# Atmega328p_sismin_attempt_4.net
KiCad netlist of a schematic drawn in EAGLE
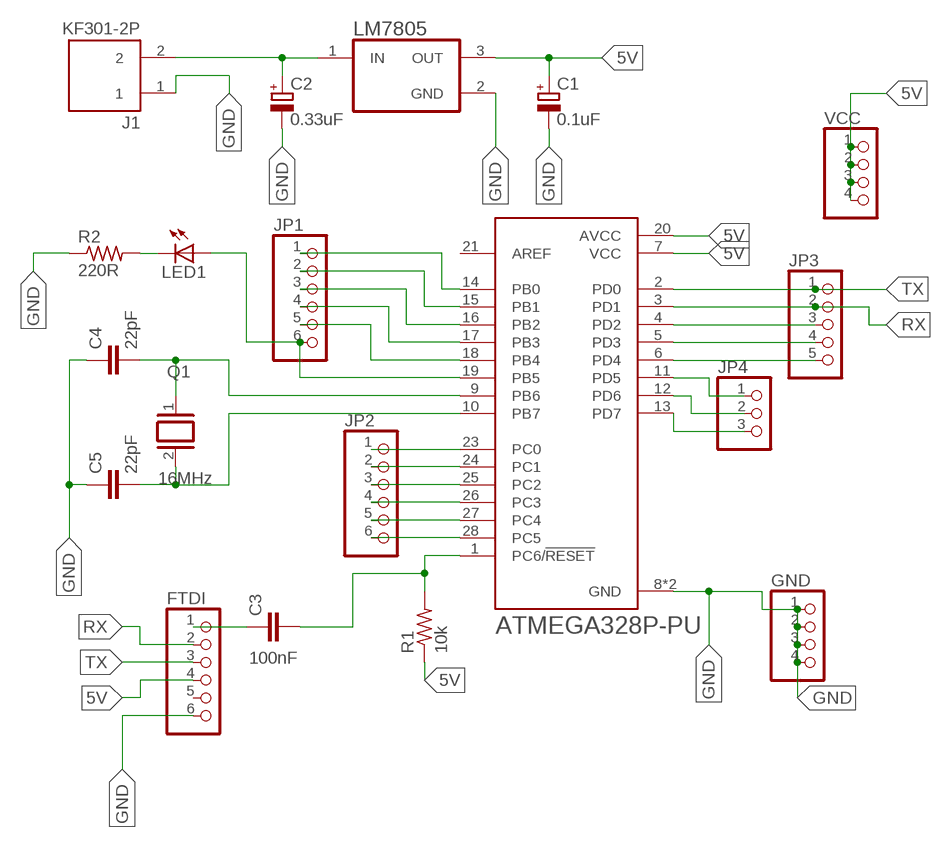
[diagram p0: schematic, sheet 1]

(export (version "E")
  (design (tool "Eeschema 10.0.6"))
  (components
    (comp (ref "C1")
      (value "0.1uF")
      (footprint "eagle-import:E2,5-6")
      (libsource (lib "eagle-import") (part "CPOL-EUE2.5-6"))
    )
    (comp (ref "C2")
      (value "0.33uF")
      (footprint "eagle-import:E2,5-6")
      (libsource (lib "eagle-import") (part "CPOL-EUE2.5-6"))
    )
    (comp (ref "C3")
      (value "100nF")
      (footprint "eagle-import:C050-025X075")
      (libsource (lib "eagle-import") (part "C-EU050-025X075"))
    )
    (comp (ref "C4")
      (value "22pF")
      (footprint "eagle-import:C025-025X050")
      (libsource (lib "eagle-import") (part "C-EU025-025X050"))
    )
    (comp (ref "C5")
      (value "22pF")
      (footprint "eagle-import:C025-025X050")
      (libsource (lib "eagle-import") (part "C-EU025-025X050"))
    )
    (comp (ref "FTDI")
      (value "PINHD-1X6")
      (footprint "eagle-import:1X06")
      (libsource (lib "eagle-import") (part "PINHD-1X6"))
    )
    (comp (ref "GND")
      (value "PINHD-1X4")
      (footprint "eagle-import:1X04")
      (libsource (lib "eagle-import") (part "PINHD-1X4"))
    )
    (comp (ref "J1")
      (value "KF301-2P")
      (footprint "eagle-import:HANDSON_KF301-2P")
      (fields (field (name "MF") "Handson Technology"))
      (libsource (lib "eagle-import") (part "KF301-2P"))
    )
    (comp (ref "JP1")
      (value "PINHD-1X6")
      (footprint "eagle-import:1X06")
      (libsource (lib "eagle-import") (part "PINHD-1X6"))
    )
    (comp (ref "JP2")
      (value "PINHD-1X6")
      (footprint "eagle-import:1X06")
      (libsource (lib "eagle-import") (part "PINHD-1X6"))
    )
    (comp (ref "JP3")
      (value "PINHD-1X5")
      (footprint "eagle-import:1X05")
      (libsource (lib "eagle-import") (part "PINHD-1X5"))
    )
    (comp (ref "JP4")
      (value "PINHD-1X3")
      (footprint "eagle-import:1X03")
      (libsource (lib "eagle-import") (part "PINHD-1X3"))
    )
    (comp (ref "LED1")
      (value "LED5MM")
      (footprint "eagle-import:LED5MM")
      (libsource (lib "eagle-import") (part "LED5MM"))
    )
    (comp (ref "LM7805")
      (value "LM7805CT/NOPB")
      (footprint "eagle-import:TO254P1054X470X2600-3")
      (fields (field (name "MF") "ON Semiconductor") (field (name "MP") "LM7805CT"))
      (libsource (lib "eagle-import") (part "LM7805CT/NOPB"))
    )
    (comp (ref "Q1")
      (value "16MHz")
      (footprint "eagle-import:QS")
      (libsource (lib "eagle-import") (part "XTAL/S"))
    )
    (comp (ref "R1")
      (value "10k")
      (footprint "eagle-import:0207_7")
      (libsource (lib "eagle-import") (part "R-US_0207/7"))
    )
    (comp (ref "R2")
      (value "220R")
      (footprint "eagle-import:0204_7")
      (libsource (lib "eagle-import") (part "R-US_0204/7"))
    )
    (comp (ref "U1")
      (value "ATMEGA328P-PU")
      (footprint "eagle-import:DIP794W46P254L2967H457Q28B")
      (fields (field (name "MF") "Microchip"))
      (libsource (lib "eagle-import") (part "ATMEGA328P-PU"))
    )
    (comp (ref "VCC")
      (value "PINHD-1X4")
      (footprint "eagle-import:1X04")
      (libsource (lib "eagle-import") (part "PINHD-1X4"))
    )
  )
  (nets
    (net (code "1") (name "5V") (class "Default")
      (node (ref "C1") (pin "+") (pinfunction "+_+") (pintype "passive"))
      (node (ref "FTDI") (pin "4") (pinfunction "4_4") (pintype "passive"))
      (node (ref "LM7805") (pin "3") (pinfunction "OUT_3") (pintype "output"))
      (node (ref "R1") (pin "1") (pinfunction "1_1") (pintype "passive"))
      (node (ref "U1") (pin "20") (pinfunction "AVCC_20") (pintype "power_in"))
      (node (ref "U1") (pin "7") (pinfunction "VCC_7") (pintype "power_in"))
      (node (ref "VCC") (pin "1") (pinfunction "1_1") (pintype "passive"))
      (node (ref "VCC") (pin "2") (pinfunction "2_2") (pintype "passive"))
      (node (ref "VCC") (pin "3") (pinfunction "3_3") (pintype "passive"))
      (node (ref "VCC") (pin "4") (pinfunction "4_4") (pintype "passive"))
    )
    (net (code "2") (name "GND") (class "Default")
      (node (ref "C1") (pin "-") (pinfunction "-_-") (pintype "passive"))
      (node (ref "C2") (pin "-") (pinfunction "-_-") (pintype "passive"))
      (node (ref "C4") (pin "1") (pinfunction "1_1") (pintype "passive"))
      (node (ref "C5") (pin "1") (pinfunction "1_1") (pintype "passive"))
      (node (ref "FTDI") (pin "6") (pinfunction "6_6") (pintype "passive"))
      (node (ref "GND") (pin "1") (pinfunction "1_1") (pintype "passive"))
      (node (ref "GND") (pin "2") (pinfunction "2_2") (pintype "passive"))
      (node (ref "GND") (pin "3") (pinfunction "3_3") (pintype "passive"))
      (node (ref "GND") (pin "4") (pinfunction "4_4") (pintype "passive"))
      (node (ref "J1") (pin "1") (pinfunction "1_1") (pintype "passive"))
      (node (ref "LM7805") (pin "2") (pinfunction "GND_2") (pintype "power_in"))
      (node (ref "R2") (pin "1") (pinfunction "1_1") (pintype "passive"))
      (node (ref "U1") (pin "22") (pinfunction "GND_22") (pintype "power_in"))
      (node (ref "U1") (pin "8") (pinfunction "GND_8") (pintype "power_in"))
    )
    (net (code "3") (name "Net-(C3-Pad1)") (class "Default")
      (node (ref "C3") (pin "1") (pinfunction "1_1") (pintype "passive"))
      (node (ref "FTDI") (pin "1") (pinfunction "1_1") (pintype "passive"))
    )
    (net (code "4") (name "Net-(LED1-C)") (class "Default")
      (node (ref "LED1") (pin "K") (pinfunction "C_K") (pintype "passive"))
      (node (ref "R2") (pin "2") (pinfunction "2_2") (pintype "passive"))
    )
    (net (code "5") (name "Net-(LM7805-IN)") (class "Default")
      (node (ref "C2") (pin "+") (pinfunction "+_+") (pintype "passive"))
      (node (ref "J1") (pin "2") (pinfunction "2_2") (pintype "passive"))
      (node (ref "LM7805") (pin "1") (pinfunction "IN_1") (pintype "input"))
    )
    (net (code "6") (name "Net-(U1-PB0)") (class "Default")
      (node (ref "JP1") (pin "1") (pinfunction "1_1") (pintype "passive"))
      (node (ref "U1") (pin "14") (pinfunction "PB0_14") (pintype "bidirectional"))
    )
    (net (code "7") (name "Net-(U1-PB1)") (class "Default")
      (node (ref "JP1") (pin "2") (pinfunction "2_2") (pintype "passive"))
      (node (ref "U1") (pin "15") (pinfunction "PB1_15") (pintype "bidirectional"))
    )
    (net (code "8") (name "Net-(U1-PB2)") (class "Default")
      (node (ref "JP1") (pin "3") (pinfunction "3_3") (pintype "passive"))
      (node (ref "U1") (pin "16") (pinfunction "PB2_16") (pintype "bidirectional"))
    )
    (net (code "9") (name "Net-(U1-PB3)") (class "Default")
      (node (ref "JP1") (pin "4") (pinfunction "4_4") (pintype "passive"))
      (node (ref "U1") (pin "17") (pinfunction "PB3_17") (pintype "bidirectional"))
    )
    (net (code "10") (name "Net-(U1-PB4)") (class "Default")
      (node (ref "JP1") (pin "5") (pinfunction "5_5") (pintype "passive"))
      (node (ref "U1") (pin "18") (pinfunction "PB4_18") (pintype "bidirectional"))
    )
    (net (code "11") (name "Net-(U1-PB5)") (class "Default")
      (node (ref "JP1") (pin "6") (pinfunction "6_6") (pintype "passive"))
      (node (ref "LED1") (pin "A") (pinfunction "A_A") (pintype "passive"))
      (node (ref "U1") (pin "19") (pinfunction "PB5_19") (pintype "bidirectional"))
    )
    (net (code "12") (name "Net-(U1-PB6)") (class "Default")
      (node (ref "C4") (pin "2") (pinfunction "2_2") (pintype "passive"))
      (node (ref "Q1") (pin "1") (pinfunction "1_1") (pintype "passive"))
      (node (ref "U1") (pin "9") (pinfunction "PB6_9") (pintype "bidirectional"))
    )
    (net (code "13") (name "Net-(U1-PB7)") (class "Default")
      (node (ref "C5") (pin "2") (pinfunction "2_2") (pintype "passive"))
      (node (ref "Q1") (pin "2") (pinfunction "2_2") (pintype "passive"))
      (node (ref "U1") (pin "10") (pinfunction "PB7_10") (pintype "bidirectional"))
    )
    (net (code "14") (name "Net-(U1-PC0)") (class "Default")
      (node (ref "JP2") (pin "1") (pinfunction "1_1") (pintype "passive"))
      (node (ref "U1") (pin "23") (pinfunction "PC0_23") (pintype "bidirectional"))
    )
    (net (code "15") (name "Net-(U1-PC1)") (class "Default")
      (node (ref "JP2") (pin "2") (pinfunction "2_2") (pintype "passive"))
      (node (ref "U1") (pin "24") (pinfunction "PC1_24") (pintype "bidirectional"))
    )
    (net (code "16") (name "Net-(U1-PC2)") (class "Default")
      (node (ref "JP2") (pin "3") (pinfunction "3_3") (pintype "passive"))
      (node (ref "U1") (pin "25") (pinfunction "PC2_25") (pintype "bidirectional"))
    )
    (net (code "17") (name "Net-(U1-PC3)") (class "Default")
      (node (ref "JP2") (pin "4") (pinfunction "4_4") (pintype "passive"))
      (node (ref "U1") (pin "26") (pinfunction "PC3_26") (pintype "bidirectional"))
    )
    (net (code "18") (name "Net-(U1-PC4)") (class "Default")
      (node (ref "JP2") (pin "5") (pinfunction "5_5") (pintype "passive"))
      (node (ref "U1") (pin "27") (pinfunction "PC4_27") (pintype "bidirectional"))
    )
    (net (code "19") (name "Net-(U1-PC5)") (class "Default")
      (node (ref "JP2") (pin "6") (pinfunction "6_6") (pintype "passive"))
      (node (ref "U1") (pin "28") (pinfunction "PC5_28") (pintype "bidirectional"))
    )
    (net (code "20") (name "Net-(U1-PC6{slash}~{RESET})") (class "Default")
      (node (ref "C3") (pin "2") (pinfunction "2_2") (pintype "passive"))
      (node (ref "R1") (pin "2") (pinfunction "2_2") (pintype "passive"))
      (node (ref "U1") (pin "1") (pinfunction "PC6/~{RESET}_1") (pintype "bidirectional"))
    )
    (net (code "21") (name "Net-(U1-PD2)") (class "Default")
      (node (ref "JP3") (pin "3") (pinfunction "3_3") (pintype "passive"))
      (node (ref "U1") (pin "4") (pinfunction "PD2_4") (pintype "bidirectional"))
    )
    (net (code "22") (name "Net-(U1-PD3)") (class "Default")
      (node (ref "JP3") (pin "4") (pinfunction "4_4") (pintype "passive"))
      (node (ref "U1") (pin "5") (pinfunction "PD3_5") (pintype "bidirectional"))
    )
    (net (code "23") (name "Net-(U1-PD4)") (class "Default")
      (node (ref "JP3") (pin "5") (pinfunction "5_5") (pintype "passive"))
      (node (ref "U1") (pin "6") (pinfunction "PD4_6") (pintype "bidirectional"))
    )
    (net (code "24") (name "Net-(U1-PD5)") (class "Default")
      (node (ref "JP4") (pin "1") (pinfunction "1_1") (pintype "passive"))
      (node (ref "U1") (pin "11") (pinfunction "PD5_11") (pintype "bidirectional"))
    )
    (net (code "25") (name "Net-(U1-PD6)") (class "Default")
      (node (ref "JP4") (pin "2") (pinfunction "2_2") (pintype "passive"))
      (node (ref "U1") (pin "12") (pinfunction "PD6_12") (pintype "bidirectional"))
    )
    (net (code "26") (name "Net-(U1-PD7)") (class "Default")
      (node (ref "JP4") (pin "3") (pinfunction "3_3") (pintype "passive"))
      (node (ref "U1") (pin "13") (pinfunction "PD7_13") (pintype "bidirectional"))
    )
    (net (code "27") (name "RX") (class "Default")
      (node (ref "FTDI") (pin "2") (pinfunction "2_2") (pintype "passive"))
      (node (ref "JP3") (pin "2") (pinfunction "2_2") (pintype "passive"))
      (node (ref "U1") (pin "3") (pinfunction "PD1_3") (pintype "bidirectional"))
    )
    (net (code "28") (name "TX") (class "Default")
      (node (ref "FTDI") (pin "3") (pinfunction "3_3") (pintype "passive"))
      (node (ref "JP3") (pin "1") (pinfunction "1_1") (pintype "passive"))
      (node (ref "U1") (pin "2") (pinfunction "PD0_2") (pintype "bidirectional"))
    )
    (net (code "29") (name "unconnected-(FTDI-Pad5)") (class "Default")
      (node (ref "FTDI") (pin "5") (pinfunction "5_5") (pintype "passive"))
    )
    (net (code "30") (name "unconnected-(U1-AREF-Pad21)") (class "Default")
      (node (ref "U1") (pin "21") (pinfunction "AREF_21") (pintype "input"))
    )
  )
)
